# InternetRadio.net
KiCad netlist of a schematic drawn in EAGLE
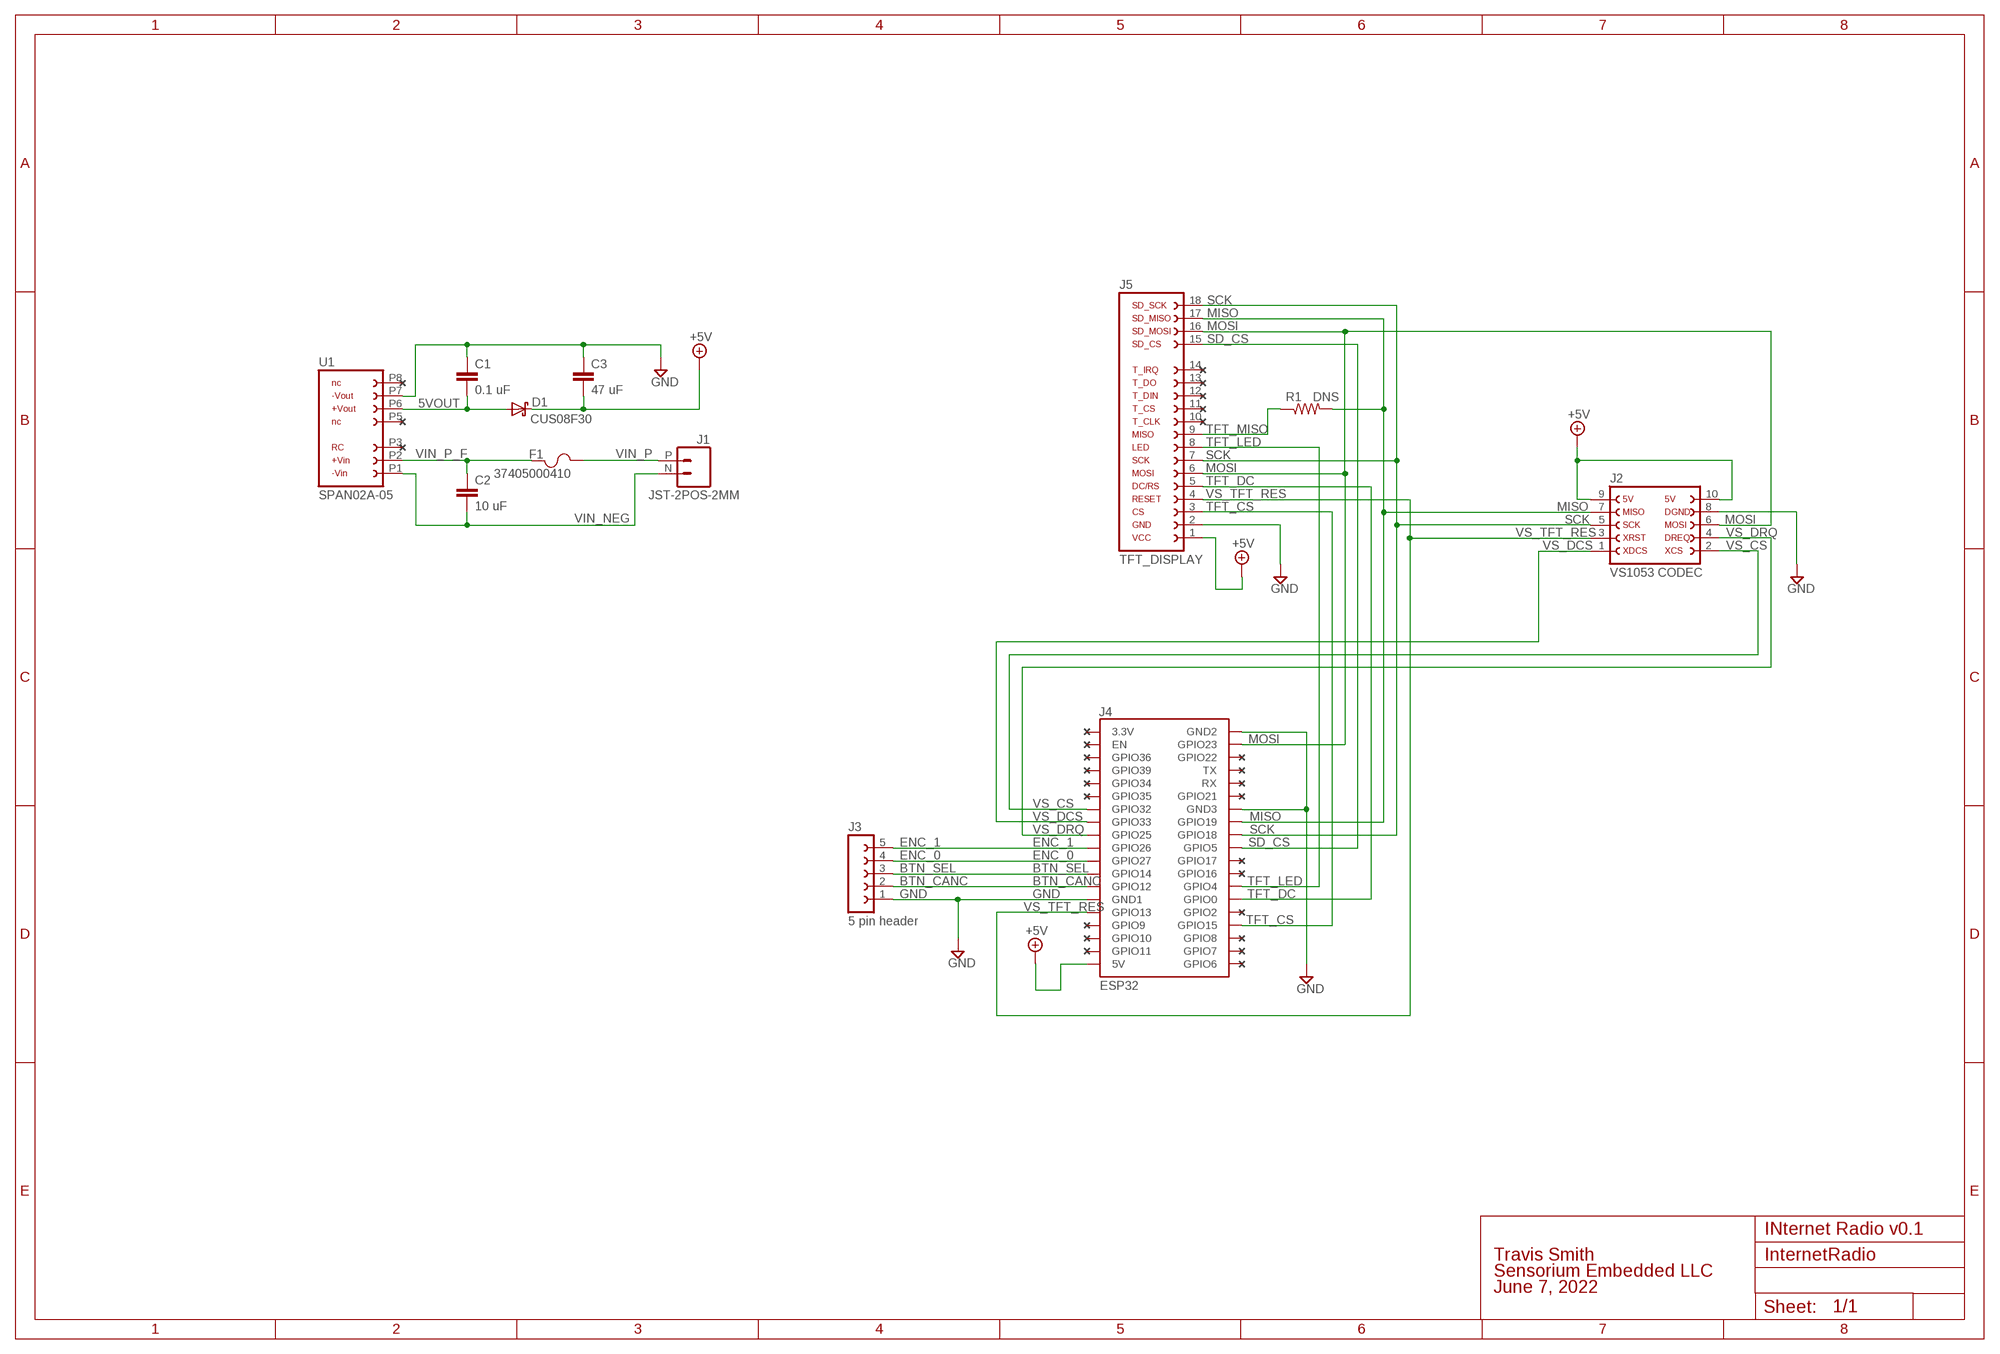
[diagram p0: schematic, sheet 1]

(export (version "E")
  (design (tool "Eeschema 10.0.6"))
  (components
    (comp (ref "C1")
      (value "0.1 uF")
      (footprint "eagle-import:0805")
      (libsource (lib "eagle-import") (part "CAP-0805-1UF-25V"))
    )
    (comp (ref "C2")
      (value "10 uF")
      (footprint "eagle-import:0805")
      (libsource (lib "eagle-import") (part "CAP-0805-1UF-25V"))
    )
    (comp (ref "C3")
      (value "47 uF")
      (footprint "eagle-import:0805")
      (libsource (lib "eagle-import") (part "CAP-0805-1UF-25V"))
    )
    (comp (ref "D1")
      (value "CUS08F30")
      (footprint "eagle-import:SOD-323")
      (libsource (lib "eagle-import") (part "SCHOTTKY_CUS08F30"))
    )
    (comp (ref "F1")
      (value "37405000410")
      (footprint "eagle-import:FUS_LITTELFUSE_374_LTF")
      (fields (field (name "COPYRIGHT") "Copyright (C) 2022 Ultra Librarian. All rights reserved."))
      (libsource (lib "eagle-import") (part "37405000410"))
    )
    (comp (ref "J1")
      (value "JST-2POS-2MM")
      (footprint "eagle-import:89400-0220")
      (libsource (lib "eagle-import") (part "JST-2POS_2MM"))
    )
    (comp (ref "J2")
      (value "VS1053 CODEC")
      (footprint "eagle-import:VS1053_MODULE")
      (libsource (lib "eagle-import") (part "VS1053_MODULE"))
    )
    (comp (ref "J3")
      (value "5 pin header")
      (footprint "eagle-import:FE05-1")
      (libsource (lib "eagle-import") (part "FE05-1"))
    )
    (comp (ref "J4")
      (value "ESP32")
      (footprint "eagle-import:ESP32")
      (libsource (lib "eagle-import") (part "ESP32"))
    )
    (comp (ref "J5")
      (value "TFT_DISPLAY")
      (footprint "eagle-import:3.5__TFT_DISPLAY-NO_HOLES")
      (libsource (lib "eagle-import") (part "3.5{dblquote}_TFT_DISPLAY"))
    )
    (comp (ref "R1")
      (value "DNS")
      (footprint "eagle-import:0805")
      (libsource (lib "eagle-import") (part "RESISTOR-0805-DNS"))
    )
    (comp (ref "U1")
      (value "SPAN02A-05")
      (footprint "eagle-import:SPAN02A-05")
      (libsource (lib "eagle-import") (part "SPAN02A-05"))
    )
  )
  (nets
    (net (code "1") (name "+5V") (class "Default")
      (node (ref "C3") (pin "2") (pinfunction "2_2") (pintype "passive"))
      (node (ref "D1") (pin "C") (pinfunction "C_C") (pintype "passive"))
      (node (ref "J2") (pin "10") (pinfunction "10_10") (pintype "passive"))
      (node (ref "J2") (pin "9") (pinfunction "9_9") (pintype "passive"))
      (node (ref "J4") (pin "5V") (pinfunction "5V_5V") (pintype "bidirectional"))
      (node (ref "J5") (pin "1") (pinfunction "1_1") (pintype "passive"))
    )
    (net (code "2") (name "/5VOUT") (class "Default")
      (node (ref "C1") (pin "2") (pinfunction "2_2") (pintype "passive"))
      (node (ref "D1") (pin "A") (pinfunction "A_A") (pintype "passive"))
      (node (ref "U1") (pin "P6") (pinfunction "6_P6") (pintype "passive"))
    )
    (net (code "3") (name "/BTN_CANC") (class "Default")
      (node (ref "J3") (pin "2") (pinfunction "2_2") (pintype "passive"))
      (node (ref "J4") (pin "GPIO12") (pinfunction "GPIO12_GPIO12") (pintype "bidirectional"))
    )
    (net (code "4") (name "/BTN_SEL") (class "Default")
      (node (ref "J3") (pin "3") (pinfunction "3_3") (pintype "passive"))
      (node (ref "J4") (pin "GPIO14") (pinfunction "GPIO14_GPIO14") (pintype "bidirectional"))
    )
    (net (code "5") (name "/ENC_0") (class "Default")
      (node (ref "J3") (pin "4") (pinfunction "4_4") (pintype "passive"))
      (node (ref "J4") (pin "GPIO27") (pinfunction "GPIO27_GPIO27") (pintype "bidirectional"))
    )
    (net (code "6") (name "/ENC_1") (class "Default")
      (node (ref "J3") (pin "5") (pinfunction "5_5") (pintype "passive"))
      (node (ref "J4") (pin "GPIO26") (pinfunction "GPIO26_GPIO26") (pintype "bidirectional"))
    )
    (net (code "7") (name "/MISO") (class "Default")
      (node (ref "J2") (pin "7") (pinfunction "7_7") (pintype "passive"))
      (node (ref "J4") (pin "GPIO19") (pinfunction "GPIO19_GPIO19") (pintype "bidirectional"))
      (node (ref "J5") (pin "17") (pinfunction "17_17") (pintype "passive"))
      (node (ref "R1") (pin "2") (pinfunction "2_2") (pintype "passive"))
    )
    (net (code "8") (name "/MOSI") (class "Default")
      (node (ref "J2") (pin "6") (pinfunction "6_6") (pintype "passive"))
      (node (ref "J4") (pin "GPIO23") (pinfunction "GPIO23_GPIO23") (pintype "bidirectional"))
      (node (ref "J5") (pin "16") (pinfunction "16_16") (pintype "passive"))
      (node (ref "J5") (pin "6") (pinfunction "6_6") (pintype "passive"))
    )
    (net (code "9") (name "/SCK") (class "Default")
      (node (ref "J2") (pin "5") (pinfunction "5_5") (pintype "passive"))
      (node (ref "J4") (pin "GPIO18") (pinfunction "GPIO18_GPIO18") (pintype "bidirectional"))
      (node (ref "J5") (pin "18") (pinfunction "18_18") (pintype "passive"))
      (node (ref "J5") (pin "7") (pinfunction "7_7") (pintype "passive"))
    )
    (net (code "10") (name "/SD_CS") (class "Default")
      (node (ref "J4") (pin "GPIO5") (pinfunction "GPIO5_GPIO5") (pintype "bidirectional"))
      (node (ref "J5") (pin "15") (pinfunction "15_15") (pintype "passive"))
    )
    (net (code "11") (name "/TFT_CS") (class "Default")
      (node (ref "J4") (pin "GPIO15") (pinfunction "GPIO15_GPIO15") (pintype "bidirectional"))
      (node (ref "J5") (pin "3") (pinfunction "3_3") (pintype "passive"))
    )
    (net (code "12") (name "/TFT_DC") (class "Default")
      (node (ref "J4") (pin "GPIO0") (pinfunction "GPIO0_GPIO0") (pintype "bidirectional"))
      (node (ref "J5") (pin "5") (pinfunction "5_5") (pintype "passive"))
    )
    (net (code "13") (name "/TFT_LED") (class "Default")
      (node (ref "J4") (pin "GPIO4") (pinfunction "GPIO4_GPIO4") (pintype "bidirectional"))
      (node (ref "J5") (pin "8") (pinfunction "8_8") (pintype "passive"))
    )
    (net (code "14") (name "/TFT_MISO") (class "Default")
      (node (ref "J5") (pin "9") (pinfunction "9_9") (pintype "passive"))
      (node (ref "R1") (pin "1") (pinfunction "1_1") (pintype "passive"))
    )
    (net (code "15") (name "/VIN_NEG") (class "Default")
      (node (ref "C2") (pin "2") (pinfunction "2_2") (pintype "passive"))
      (node (ref "J1") (pin "N") (pinfunction "1_N") (pintype "passive"))
      (node (ref "U1") (pin "P1") (pinfunction "1_P1") (pintype "passive"))
    )
    (net (code "16") (name "/VIN_P") (class "Default")
      (node (ref "F1") (pin "1") (pinfunction "1_1") (pintype "passive"))
      (node (ref "J1") (pin "P") (pinfunction "2_P") (pintype "passive"))
    )
    (net (code "17") (name "/VIN_P_F") (class "Default")
      (node (ref "C2") (pin "1") (pinfunction "1_1") (pintype "passive"))
      (node (ref "F1") (pin "2") (pinfunction "2_2") (pintype "passive"))
      (node (ref "U1") (pin "P2") (pinfunction "2_P2") (pintype "passive"))
    )
    (net (code "18") (name "/VS_CS") (class "Default")
      (node (ref "J2") (pin "2") (pinfunction "2_2") (pintype "passive"))
      (node (ref "J4") (pin "GPIO32") (pinfunction "GPIO32_GPIO32") (pintype "bidirectional"))
    )
    (net (code "19") (name "/VS_DCS") (class "Default")
      (node (ref "J2") (pin "1") (pinfunction "1_1") (pintype "passive"))
      (node (ref "J4") (pin "GPIO33") (pinfunction "GPIO33_GPIO33") (pintype "bidirectional"))
    )
    (net (code "20") (name "/VS_DRQ") (class "Default")
      (node (ref "J2") (pin "4") (pinfunction "4_4") (pintype "passive"))
      (node (ref "J4") (pin "GPIO25") (pinfunction "GPIO25_GPIO25") (pintype "bidirectional"))
    )
    (net (code "21") (name "/VS_TFT_RES") (class "Default")
      (node (ref "J2") (pin "3") (pinfunction "3_3") (pintype "passive"))
      (node (ref "J4") (pin "GPIO13") (pinfunction "GPIO13_GPIO13") (pintype "bidirectional"))
      (node (ref "J5") (pin "4") (pinfunction "4_4") (pintype "passive"))
    )
    (net (code "22") (name "GND") (class "Default")
      (node (ref "C1") (pin "1") (pinfunction "1_1") (pintype "passive"))
      (node (ref "C3") (pin "1") (pinfunction "1_1") (pintype "passive"))
      (node (ref "J2") (pin "8") (pinfunction "8_8") (pintype "passive"))
      (node (ref "J3") (pin "1") (pinfunction "1_1") (pintype "passive"))
      (node (ref "J4") (pin "GND1") (pinfunction "GND1_GND1") (pintype "bidirectional"))
      (node (ref "J4") (pin "GND2") (pinfunction "GND2_GND2") (pintype "bidirectional"))
      (node (ref "J4") (pin "GND3") (pinfunction "GND3_GND3") (pintype "bidirectional"))
      (node (ref "J5") (pin "2") (pinfunction "2_2") (pintype "passive"))
      (node (ref "U1") (pin "P7") (pinfunction "7_P7") (pintype "passive"))
    )
    (net (code "23") (name "unconnected-(J4-Pad3.3V)") (class "Default")
      (node (ref "J4") (pin "3.3V") (pinfunction "3.3V_3.3V") (pintype "bidirectional"))
    )
    (net (code "24") (name "unconnected-(J4-PadEN)") (class "Default")
      (node (ref "J4") (pin "EN") (pinfunction "EN_EN") (pintype "bidirectional"))
    )
    (net (code "25") (name "unconnected-(J4-PadGPIO2)") (class "Default")
      (node (ref "J4") (pin "GPIO2") (pinfunction "GPIO2_GPIO2") (pintype "bidirectional"))
    )
    (net (code "26") (name "unconnected-(J4-PadGPIO6)") (class "Default")
      (node (ref "J4") (pin "GPIO6") (pinfunction "GPIO6_GPIO6") (pintype "bidirectional"))
    )
    (net (code "27") (name "unconnected-(J4-PadGPIO7)") (class "Default")
      (node (ref "J4") (pin "GPIO7") (pinfunction "GPIO7_GPIO7") (pintype "bidirectional"))
    )
    (net (code "28") (name "unconnected-(J4-PadGPIO8)") (class "Default")
      (node (ref "J4") (pin "GPIO8") (pinfunction "GPIO8_GPIO8") (pintype "bidirectional"))
    )
    (net (code "29") (name "unconnected-(J4-PadGPIO9)") (class "Default")
      (node (ref "J4") (pin "GPIO9") (pinfunction "GPIO9_GPIO9") (pintype "bidirectional"))
    )
    (net (code "30") (name "unconnected-(J4-PadGPIO10)") (class "Default")
      (node (ref "J4") (pin "GPIO10") (pinfunction "GPIO10_GPIO10") (pintype "bidirectional"))
    )
    (net (code "31") (name "unconnected-(J4-PadGPIO11)") (class "Default")
      (node (ref "J4") (pin "GPIO11") (pinfunction "GPIO11_GPIO11") (pintype "bidirectional"))
    )
    (net (code "32") (name "unconnected-(J4-PadGPIO16)") (class "Default")
      (node (ref "J4") (pin "GPIO16") (pinfunction "GPIO16_GPIO16") (pintype "bidirectional"))
    )
    (net (code "33") (name "unconnected-(J4-PadGPIO17)") (class "Default")
      (node (ref "J4") (pin "GPIO17") (pinfunction "GPIO17_GPIO17") (pintype "bidirectional"))
    )
    (net (code "34") (name "unconnected-(J4-PadGPIO21)") (class "Default")
      (node (ref "J4") (pin "GPIO21") (pinfunction "GPIO21_GPIO21") (pintype "bidirectional"))
    )
    (net (code "35") (name "unconnected-(J4-PadGPIO22)") (class "Default")
      (node (ref "J4") (pin "GPIO22") (pinfunction "GPIO22_GPIO22") (pintype "bidirectional"))
    )
    (net (code "36") (name "unconnected-(J4-PadGPIO34)") (class "Default")
      (node (ref "J4") (pin "GPIO34") (pinfunction "GPIO34_GPIO34") (pintype "bidirectional"))
    )
    (net (code "37") (name "unconnected-(J4-PadGPIO35)") (class "Default")
      (node (ref "J4") (pin "GPIO35") (pinfunction "GPIO35_GPIO35") (pintype "bidirectional"))
    )
    (net (code "38") (name "unconnected-(J4-PadGPIO36)") (class "Default")
      (node (ref "J4") (pin "GPIO36") (pinfunction "GPIO36_GPIO36") (pintype "bidirectional"))
    )
    (net (code "39") (name "unconnected-(J4-PadGPIO39)") (class "Default")
      (node (ref "J4") (pin "GPIO39") (pinfunction "GPIO39_GPIO39") (pintype "bidirectional"))
    )
    (net (code "40") (name "unconnected-(J4-PadRX)") (class "Default")
      (node (ref "J4") (pin "RX") (pinfunction "RX_RX") (pintype "bidirectional"))
    )
    (net (code "41") (name "unconnected-(J4-PadTX)") (class "Default")
      (node (ref "J4") (pin "TX") (pinfunction "TX_TX") (pintype "bidirectional"))
    )
    (net (code "42") (name "unconnected-(J5-Pad10)") (class "Default")
      (node (ref "J5") (pin "10") (pinfunction "10_10") (pintype "passive"))
    )
    (net (code "43") (name "unconnected-(J5-Pad11)") (class "Default")
      (node (ref "J5") (pin "11") (pinfunction "11_11") (pintype "passive"))
    )
    (net (code "44") (name "unconnected-(J5-Pad12)") (class "Default")
      (node (ref "J5") (pin "12") (pinfunction "12_12") (pintype "passive"))
    )
    (net (code "45") (name "unconnected-(J5-Pad13)") (class "Default")
      (node (ref "J5") (pin "13") (pinfunction "13_13") (pintype "passive"))
    )
    (net (code "46") (name "unconnected-(J5-Pad14)") (class "Default")
      (node (ref "J5") (pin "14") (pinfunction "14_14") (pintype "passive"))
    )
    (net (code "47") (name "unconnected-(U1-3-PadP3)") (class "Default")
      (node (ref "U1") (pin "P3") (pinfunction "3_P3") (pintype "passive"))
    )
    (net (code "48") (name "unconnected-(U1-5-PadP5)") (class "Default")
      (node (ref "U1") (pin "P5") (pinfunction "5_P5") (pintype "passive"))
    )
    (net (code "49") (name "unconnected-(U1-8-PadP8)") (class "Default")
      (node (ref "U1") (pin "P8") (pinfunction "8_P8") (pintype "passive"))
    )
  )
)
